# ArduinoBoardMKII.net
KiCad netlist of a schematic drawn in EAGLE
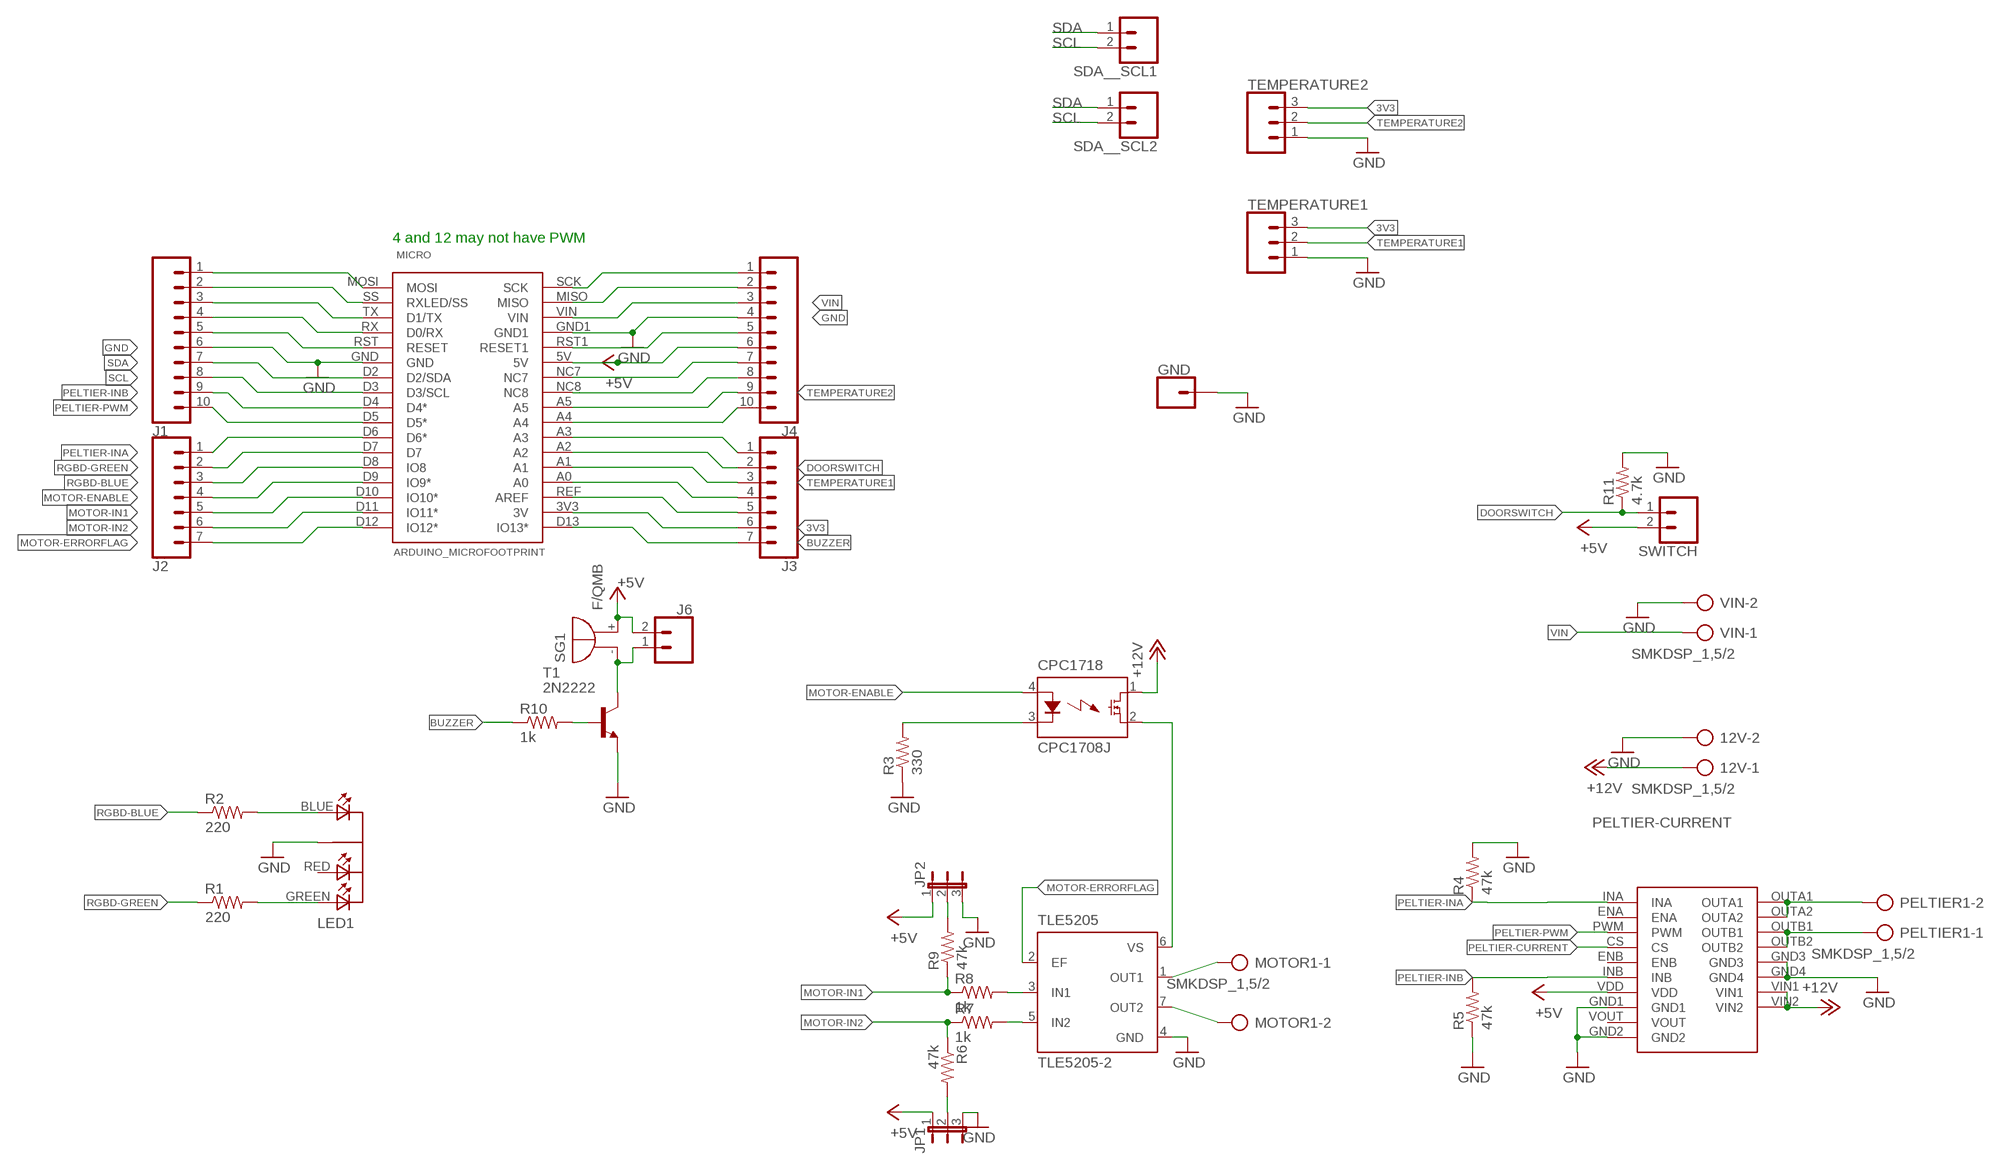
[diagram p0: schematic, sheet 1]

(export (version "E")
  (design (tool "Eeschema 10.0.6"))
  (components
    (comp (ref "12V")
      (value "SMKDSP_1,5/2")
      (footprint "eagle-import:SMKDSP_1,5_2")
      (fields (field (name "MF") "FARNELL") (field (name "MPN") "1733570"))
      (libsource (lib "eagle-import") (part "SMKDSP_1,5/2"))
    )
    (comp (ref "CPC1718")
      (value "CPC1708J")
      (footprint "eagle-import:I4-PAC")
      (libsource (lib "eagle-import") (part "CPC1708J"))
    )
    (comp (ref "GND")
      (value "CONN_01")
      (footprint "eagle-import:1X01")
      (libsource (lib "eagle-import") (part "CONN_01"))
    )
    (comp (ref "J1")
      (value "CONN_10LOCK")
      (footprint "eagle-import:1X10_LOCK")
      (libsource (lib "eagle-import") (part "CONN_10LOCK"))
    )
    (comp (ref "J2")
      (value "CONN_07LOCK")
      (footprint "eagle-import:1X07_LOCK")
      (libsource (lib "eagle-import") (part "CONN_07LOCK"))
    )
    (comp (ref "J3")
      (value "CONN_07LOCK")
      (footprint "eagle-import:1X07_LOCK")
      (libsource (lib "eagle-import") (part "CONN_07LOCK"))
    )
    (comp (ref "J4")
      (value "CONN_10LOCK")
      (footprint "eagle-import:1X10_LOCK")
      (libsource (lib "eagle-import") (part "CONN_10LOCK"))
    )
    (comp (ref "J6")
      (value "CONN_021X02_NO_SILK")
      (footprint "eagle-import:1X02_NO_SILK")
      (libsource (lib "eagle-import") (part "CONN_021X02_NO_SILK"))
    )
    (comp (ref "JP1")
      (value "JP2E")
      (footprint "eagle-import:JP2")
      (libsource (lib "eagle-import") (part "JP2E"))
    )
    (comp (ref "JP2")
      (value "JP2E")
      (footprint "eagle-import:JP2")
      (libsource (lib "eagle-import") (part "JP2E"))
    )
    (comp (ref "LED1")
      (value "LED-DIP-3")
      (footprint "eagle-import:DIP-4")
      (libsource (lib "eagle-import") (part "LED-DIP-3"))
    )
    (comp (ref "MICRO")
      (value "ARDUINO_MICROFOOTPRINT")
      (footprint "eagle-import:ARDUINO-MICRO")
      (libsource (lib "eagle-import") (part "ARDUINO_MICROFOOTPRINT"))
    )
    (comp (ref "MOTOR1")
      (value "SMKDSP_1,5/2")
      (footprint "eagle-import:SMKDSP_1,5_2")
      (fields (field (name "MF") "FARNELL") (field (name "MPN") "1733570"))
      (libsource (lib "eagle-import") (part "SMKDSP_1,5/2"))
    )
    (comp (ref "PELTIER1")
      (value "SMKDSP_1,5/2")
      (footprint "eagle-import:SMKDSP_1,5_2")
      (fields (field (name "MF") "FARNELL") (field (name "MPN") "1733570"))
      (libsource (lib "eagle-import") (part "SMKDSP_1,5/2"))
    )
    (comp (ref "R1")
      (value "220")
      (footprint "eagle-import:0207_10")
      (libsource (lib "eagle-import") (part "R-US_0207/10"))
    )
    (comp (ref "R2")
      (value "220")
      (footprint "eagle-import:0207_10")
      (libsource (lib "eagle-import") (part "R-US_0207/10"))
    )
    (comp (ref "R3")
      (value "330")
      (footprint "eagle-import:0207_10")
      (libsource (lib "eagle-import") (part "R-US_0207/10"))
    )
    (comp (ref "R4")
      (value "47k")
      (footprint "eagle-import:0207_10")
      (libsource (lib "eagle-import") (part "resistor_348_R-US_0207/10"))
    )
    (comp (ref "R5")
      (value "47k")
      (footprint "eagle-import:0207_10")
      (libsource (lib "eagle-import") (part "resistor_348_R-US_0207/10"))
    )
    (comp (ref "R6")
      (value "47k")
      (footprint "eagle-import:0207_12")
      (libsource (lib "eagle-import") (part "resistor_348_R-US_0207/12"))
    )
    (comp (ref "R7")
      (value "1k")
      (footprint "eagle-import:0207_12")
      (libsource (lib "eagle-import") (part "resistor_348_R-US_0207/12"))
    )
    (comp (ref "R8")
      (value "1k")
      (footprint "eagle-import:0207_12")
      (libsource (lib "eagle-import") (part "resistor_348_R-US_0207/12"))
    )
    (comp (ref "R9")
      (value "47k")
      (footprint "eagle-import:0207_12")
      (libsource (lib "eagle-import") (part "resistor_348_R-US_0207/12"))
    )
    (comp (ref "R10")
      (value "1k")
      (footprint "eagle-import:0207_7")
      (libsource (lib "eagle-import") (part "rcl_334_R-US_0207/7"))
    )
    (comp (ref "R11")
      (value "4.7k")
      (footprint "eagle-import:0207_10")
      (libsource (lib "eagle-import") (part "R-US_0207/10"))
    )
    (comp (ref "SDA__SCL1")
      (value "CONN_02PTH3")
      (footprint "eagle-import:1X02_LONGPADS")
      (libsource (lib "eagle-import") (part "CONN_02PTH3"))
    )
    (comp (ref "SDA__SCL2")
      (value "CONN_02PTH3")
      (footprint "eagle-import:1X02_LONGPADS")
      (libsource (lib "eagle-import") (part "CONN_02PTH3"))
    )
    (comp (ref "SG1")
      (value "F/QMB")
      (footprint "eagle-import:F_QMB")
      (libsource (lib "eagle-import") (part "F/QMB"))
    )
    (comp (ref "SWITCH")
      (value "CONN_02PTH3")
      (footprint "eagle-import:1X02_LONGPADS")
      (libsource (lib "eagle-import") (part "CONN_02PTH3"))
    )
    (comp (ref "T1")
      (value "2N2222")
      (footprint "eagle-import:TO18")
      (libsource (lib "eagle-import") (part "2N2222"))
    )
    (comp (ref "TEMPERATURE1")
      (value "CONN_03LONGPADS")
      (footprint "eagle-import:1X03_LONGPADS")
      (libsource (lib "eagle-import") (part "CONN_03LONGPADS"))
    )
    (comp (ref "TEMPERATURE2")
      (value "CONN_03LONGPADS")
      (footprint "eagle-import:1X03_LONGPADS")
      (libsource (lib "eagle-import") (part "CONN_03LONGPADS"))
    )
    (comp (ref "TLE5205")
      (value "TLE5205-2")
      (footprint "eagle-import:P-TO220-7-11")
      (libsource (lib "eagle-import") (part "TLE5205-2"))
    )
    (comp (ref "VIN")
      (value "SMKDSP_1,5/2")
      (footprint "eagle-import:SMKDSP_1,5_2")
      (fields (field (name "MF") "FARNELL") (field (name "MPN") "1733570"))
      (libsource (lib "eagle-import") (part "SMKDSP_1,5/2"))
    )
    (comp (ref "VNH5019")
      (value "VNH5019VNH5019BOARD")
      (footprint "eagle-import:DIP3302W60P254L2400H500Q20B")
      (libsource (lib "eagle-import") (part "VNH5019VNH5019BOARD"))
    )
  )
  (nets
    (net (code "1") (name "+5V") (class "Default")
      (node (ref "J4") (pin "6") (pinfunction "6_6") (pintype "passive"))
      (node (ref "J6") (pin "2") (pinfunction "2_2") (pintype "passive"))
      (node (ref "JP1") (pin "1") (pinfunction "1_1") (pintype "passive"))
      (node (ref "JP2") (pin "1") (pinfunction "1_1") (pintype "passive"))
      (node (ref "MICRO") (pin "5V") (pinfunction "5V_5V") (pintype "bidirectional"))
      (node (ref "SG1") (pin "+") (pinfunction "-_+") (pintype "passive"))
      (node (ref "SWITCH") (pin "2") (pinfunction "2_2") (pintype "passive"))
      (node (ref "VNH5019") (pin "VDD") (pinfunction "VDD_VDD") (pintype "bidirectional"))
    )
    (net (code "2") (name "+12V") (class "Default")
      (node (ref "12V") (pin "1") (pinfunction "KL_1") (pintype "passive"))
      (node (ref "CPC1718") (pin "1") (pinfunction "DS1_1") (pintype "passive"))
      (node (ref "VNH5019") (pin "VIN1") (pinfunction "VIN1_VIN1") (pintype "bidirectional"))
      (node (ref "VNH5019") (pin "VIN2") (pinfunction "VIN2_VIN2") (pintype "bidirectional"))
    )
    (net (code "3") (name "3V3") (class "Default")
      (node (ref "J3") (pin "6") (pinfunction "6_6") (pintype "passive"))
      (node (ref "MICRO") (pin "3V3") (pinfunction "3V_3V3") (pintype "bidirectional"))
      (node (ref "TEMPERATURE1") (pin "3") (pinfunction "3_3") (pintype "passive"))
      (node (ref "TEMPERATURE2") (pin "3") (pinfunction "3_3") (pintype "passive"))
    )
    (net (code "4") (name "BUZZER") (class "Default")
      (node (ref "J3") (pin "7") (pinfunction "7_7") (pintype "passive"))
      (node (ref "MICRO") (pin "D13") (pinfunction "IO13*_D13") (pintype "bidirectional"))
      (node (ref "R10") (pin "1") (pinfunction "1_1") (pintype "passive"))
    )
    (net (code "5") (name "DOORSWITCH") (class "Default")
      (node (ref "J3") (pin "2") (pinfunction "2_2") (pintype "passive"))
      (node (ref "MICRO") (pin "A2") (pinfunction "A2_A2") (pintype "bidirectional"))
      (node (ref "R11") (pin "1") (pinfunction "1_1") (pintype "passive"))
      (node (ref "SWITCH") (pin "1") (pinfunction "1_1") (pintype "passive"))
    )
    (net (code "6") (name "GND") (class "Default")
      (node (ref "12V") (pin "2") (pinfunction "KL_2") (pintype "passive"))
      (node (ref "GND") (pin "1") (pinfunction "1_1") (pintype "passive"))
      (node (ref "J1") (pin "6") (pinfunction "6_6") (pintype "passive"))
      (node (ref "J4") (pin "4") (pinfunction "4_4") (pintype "passive"))
      (node (ref "JP1") (pin "3") (pinfunction "3_3") (pintype "passive"))
      (node (ref "JP2") (pin "3") (pinfunction "3_3") (pintype "passive"))
      (node (ref "LED1") (pin "COMMON_CATHODE") (pinfunction "COM-CATHODE_COMMON_CATHODE") (pintype "passive"))
      (node (ref "MICRO") (pin "GND") (pinfunction "GND_GND") (pintype "bidirectional"))
      (node (ref "MICRO") (pin "GND1") (pinfunction "GND1_GND1") (pintype "bidirectional"))
      (node (ref "R11") (pin "2") (pinfunction "2_2") (pintype "passive"))
      (node (ref "R3") (pin "1") (pinfunction "1_1") (pintype "passive"))
      (node (ref "R4") (pin "2") (pinfunction "2_2") (pintype "passive"))
      (node (ref "R5") (pin "1") (pinfunction "1_1") (pintype "passive"))
      (node (ref "T1") (pin "1") (pinfunction "E_1") (pintype "passive"))
      (node (ref "TEMPERATURE1") (pin "1") (pinfunction "1_1") (pintype "passive"))
      (node (ref "TEMPERATURE2") (pin "1") (pinfunction "1_1") (pintype "passive"))
      (node (ref "TLE5205") (pin "4") (pinfunction "GND_4") (pintype "power_in"))
      (node (ref "VIN") (pin "2") (pinfunction "KL_2") (pintype "passive"))
      (node (ref "VNH5019") (pin "GND1") (pinfunction "GND1_GND1") (pintype "bidirectional"))
      (node (ref "VNH5019") (pin "GND2") (pinfunction "GND2_GND2") (pintype "bidirectional"))
      (node (ref "VNH5019") (pin "GND3") (pinfunction "GND3_GND3") (pintype "bidirectional"))
      (node (ref "VNH5019") (pin "GND4") (pinfunction "GND4_GND4") (pintype "bidirectional"))
    )
    (net (code "7") (name "MOTOR-ENABLE") (class "Default")
      (node (ref "CPC1718") (pin "4") (pinfunction "A_4") (pintype "passive"))
      (node (ref "J2") (pin "4") (pinfunction "4_4") (pintype "passive"))
      (node (ref "MICRO") (pin "D9") (pinfunction "IO9*_D9") (pintype "bidirectional"))
    )
    (net (code "8") (name "MOTOR-ERRORFLAG") (class "Default")
      (node (ref "J2") (pin "7") (pinfunction "7_7") (pintype "passive"))
      (node (ref "MICRO") (pin "D12") (pinfunction "IO12*_D12") (pintype "bidirectional"))
      (node (ref "TLE5205") (pin "2") (pinfunction "EF_2") (pintype "open_collector"))
    )
    (net (code "9") (name "MOTOR-IN1") (class "Default")
      (node (ref "J2") (pin "5") (pinfunction "5_5") (pintype "passive"))
      (node (ref "MICRO") (pin "D10") (pinfunction "IO10*_D10") (pintype "bidirectional"))
      (node (ref "R8") (pin "1") (pinfunction "1_1") (pintype "passive"))
      (node (ref "R9") (pin "1") (pinfunction "1_1") (pintype "passive"))
    )
    (net (code "10") (name "MOTOR-IN2") (class "Default")
      (node (ref "J2") (pin "6") (pinfunction "6_6") (pintype "passive"))
      (node (ref "MICRO") (pin "D11") (pinfunction "IO11*_D11") (pintype "bidirectional"))
      (node (ref "R6") (pin "1") (pinfunction "1_1") (pintype "passive"))
      (node (ref "R7") (pin "1") (pinfunction "1_1") (pintype "passive"))
    )
    (net (code "11") (name "Net-(CPC1718-DS2)") (class "Default")
      (node (ref "CPC1718") (pin "2") (pinfunction "DS2_2") (pintype "passive"))
      (node (ref "TLE5205") (pin "6") (pinfunction "VS_6") (pintype "input"))
    )
    (net (code "12") (name "Net-(CPC1718-K)") (class "Default")
      (node (ref "CPC1718") (pin "3") (pinfunction "K_3") (pintype "passive"))
      (node (ref "R3") (pin "2") (pinfunction "2_2") (pintype "passive"))
    )
    (net (code "13") (name "Net-(J1-Pad1)") (class "Default")
      (node (ref "J1") (pin "1") (pinfunction "1_1") (pintype "passive"))
      (node (ref "MICRO") (pin "MOSI") (pinfunction "MOSI_MOSI") (pintype "bidirectional"))
    )
    (net (code "14") (name "Net-(J3-Pad1)") (class "Default")
      (node (ref "J3") (pin "1") (pinfunction "1_1") (pintype "passive"))
      (node (ref "MICRO") (pin "A3") (pinfunction "A3_A3") (pintype "bidirectional"))
    )
    (net (code "15") (name "Net-(J3-Pad4)") (class "Default")
      (node (ref "J3") (pin "4") (pinfunction "4_4") (pintype "passive"))
      (node (ref "MICRO") (pin "A0") (pinfunction "A0_A0") (pintype "bidirectional"))
    )
    (net (code "16") (name "Net-(J4-Pad1)") (class "Default")
      (node (ref "J4") (pin "1") (pinfunction "1_1") (pintype "passive"))
      (node (ref "MICRO") (pin "SCK") (pinfunction "SCK_SCK") (pintype "bidirectional"))
    )
    (net (code "17") (name "Net-(J4-Pad2)") (class "Default")
      (node (ref "J4") (pin "2") (pinfunction "2_2") (pintype "passive"))
      (node (ref "MICRO") (pin "MISO") (pinfunction "MISO_MISO") (pintype "bidirectional"))
    )
    (net (code "18") (name "Net-(J4-Pad7)") (class "Default")
      (node (ref "J4") (pin "7") (pinfunction "7_7") (pintype "passive"))
      (node (ref "MICRO") (pin "NC7") (pinfunction "NC7_NC7") (pintype "bidirectional"))
    )
    (net (code "19") (name "Net-(J4-Pad8)") (class "Default")
      (node (ref "J4") (pin "8") (pinfunction "8_8") (pintype "passive"))
      (node (ref "MICRO") (pin "NC8") (pinfunction "NC8_NC8") (pintype "bidirectional"))
    )
    (net (code "20") (name "Net-(J4-Pad10)") (class "Default")
      (node (ref "J4") (pin "10") (pinfunction "10_10") (pintype "passive"))
      (node (ref "MICRO") (pin "A4") (pinfunction "A4_A4") (pintype "bidirectional"))
    )
    (net (code "21") (name "Net-(JP1-Pad2)") (class "Default")
      (node (ref "JP1") (pin "2") (pinfunction "2_2") (pintype "passive"))
      (node (ref "R6") (pin "2") (pinfunction "2_2") (pintype "passive"))
    )
    (net (code "22") (name "Net-(JP2-Pad2)") (class "Default")
      (node (ref "JP2") (pin "2") (pinfunction "2_2") (pintype "passive"))
      (node (ref "R9") (pin "2") (pinfunction "2_2") (pintype "passive"))
    )
    (net (code "23") (name "Net-(LED1-PadBLUE)") (class "Default")
      (node (ref "LED1") (pin "BLUE") (pinfunction "BLUE_BLUE") (pintype "passive"))
      (node (ref "R2") (pin "2") (pinfunction "2_2") (pintype "passive"))
    )
    (net (code "24") (name "Net-(LED1-PadGREEN)") (class "Default")
      (node (ref "LED1") (pin "GREEN") (pinfunction "GREEN_GREEN") (pintype "passive"))
      (node (ref "R1") (pin "2") (pinfunction "2_2") (pintype "passive"))
    )
    (net (code "25") (name "Net-(MICRO-AREF)") (class "Default")
      (node (ref "J3") (pin "5") (pinfunction "5_5") (pintype "passive"))
      (node (ref "MICRO") (pin "REF") (pinfunction "AREF_REF") (pintype "bidirectional"))
    )
    (net (code "26") (name "Net-(MICRO-D0{slash}RX)") (class "Default")
      (node (ref "J1") (pin "4") (pinfunction "4_4") (pintype "passive"))
      (node (ref "MICRO") (pin "RX") (pinfunction "D0/RX_RX") (pintype "bidirectional"))
    )
    (net (code "27") (name "Net-(MICRO-D1{slash}TX)") (class "Default")
      (node (ref "J1") (pin "3") (pinfunction "3_3") (pintype "passive"))
      (node (ref "MICRO") (pin "TX") (pinfunction "D1/TX_TX") (pintype "bidirectional"))
    )
    (net (code "28") (name "Net-(MICRO-RESET)") (class "Default")
      (node (ref "J1") (pin "5") (pinfunction "5_5") (pintype "passive"))
      (node (ref "MICRO") (pin "RST") (pinfunction "RESET_RST") (pintype "bidirectional"))
    )
    (net (code "29") (name "Net-(MICRO-RESET1)") (class "Default")
      (node (ref "J4") (pin "5") (pinfunction "5_5") (pintype "passive"))
      (node (ref "MICRO") (pin "RST1") (pinfunction "RESET1_RST1") (pintype "bidirectional"))
    )
    (net (code "30") (name "Net-(MICRO-RXLED{slash}SS)") (class "Default")
      (node (ref "J1") (pin "2") (pinfunction "2_2") (pintype "passive"))
      (node (ref "MICRO") (pin "SS") (pinfunction "RXLED/SS_SS") (pintype "bidirectional"))
    )
    (net (code "31") (name "Net-(MOTOR1A-KL)") (class "Default")
      (node (ref "MOTOR1") (pin "1") (pinfunction "KL_1") (pintype "passive"))
      (node (ref "TLE5205") (pin "1") (pinfunction "OUT1_1") (pintype "output"))
    )
    (net (code "32") (name "Net-(MOTOR1B-KL)") (class "Default")
      (node (ref "MOTOR1") (pin "2") (pinfunction "KL_2") (pintype "passive"))
      (node (ref "TLE5205") (pin "7") (pinfunction "OUT2_7") (pintype "output"))
    )
    (net (code "33") (name "Net-(PELTIER1A-KL)") (class "Default")
      (node (ref "PELTIER1") (pin "1") (pinfunction "KL_1") (pintype "passive"))
      (node (ref "VNH5019") (pin "OUTB1") (pinfunction "OUTB1_OUTB1") (pintype "bidirectional"))
      (node (ref "VNH5019") (pin "OUTB2") (pinfunction "OUTB2_OUTB2") (pintype "bidirectional"))
    )
    (net (code "34") (name "Net-(PELTIER1B-KL)") (class "Default")
      (node (ref "PELTIER1") (pin "2") (pinfunction "KL_2") (pintype "passive"))
      (node (ref "VNH5019") (pin "OUTA1") (pinfunction "OUTA1_OUTA1") (pintype "bidirectional"))
      (node (ref "VNH5019") (pin "OUTA2") (pinfunction "OUTA2_OUTA2") (pintype "bidirectional"))
    )
    (net (code "35") (name "Net-(SG1-+)") (class "Default")
      (node (ref "J6") (pin "1") (pinfunction "1_1") (pintype "passive"))
      (node (ref "SG1") (pin "-") (pinfunction "+_-") (pintype "passive"))
      (node (ref "T1") (pin "3") (pinfunction "C_3") (pintype "passive"))
    )
    (net (code "36") (name "Net-(T1-B)") (class "Default")
      (node (ref "R10") (pin "2") (pinfunction "2_2") (pintype "passive"))
      (node (ref "T1") (pin "2") (pinfunction "B_2") (pintype "passive"))
    )
    (net (code "37") (name "Net-(TLE5205-IN1)") (class "Default")
      (node (ref "R8") (pin "2") (pinfunction "2_2") (pintype "passive"))
      (node (ref "TLE5205") (pin "3") (pinfunction "IN1_3") (pintype "input"))
    )
    (net (code "38") (name "Net-(TLE5205-IN2)") (class "Default")
      (node (ref "R7") (pin "2") (pinfunction "2_2") (pintype "passive"))
      (node (ref "TLE5205") (pin "5") (pinfunction "IN2_5") (pintype "input"))
    )
    (net (code "39") (name "PELTIER-CURRENT") (class "Default")
      (node (ref "VNH5019") (pin "CS") (pinfunction "CS_CS") (pintype "bidirectional"))
    )
    (net (code "40") (name "PELTIER-INA") (class "Default")
      (node (ref "J2") (pin "1") (pinfunction "1_1") (pintype "passive"))
      (node (ref "MICRO") (pin "D6") (pinfunction "D6*_D6") (pintype "bidirectional"))
      (node (ref "R4") (pin "1") (pinfunction "1_1") (pintype "passive"))
      (node (ref "VNH5019") (pin "INA") (pinfunction "INA_INA") (pintype "bidirectional"))
    )
    (net (code "41") (name "PELTIER-INB") (class "Default")
      (node (ref "J1") (pin "9") (pinfunction "9_9") (pintype "passive"))
      (node (ref "MICRO") (pin "D4") (pinfunction "D4*_D4") (pintype "bidirectional"))
      (node (ref "R5") (pin "2") (pinfunction "2_2") (pintype "passive"))
      (node (ref "VNH5019") (pin "INB") (pinfunction "INB_INB") (pintype "bidirectional"))
    )
    (net (code "42") (name "PELTIER-PWM") (class "Default")
      (node (ref "J1") (pin "10") (pinfunction "10_10") (pintype "passive"))
      (node (ref "MICRO") (pin "D5") (pinfunction "D5*_D5") (pintype "bidirectional"))
      (node (ref "VNH5019") (pin "PWM") (pinfunction "PWM_PWM") (pintype "bidirectional"))
    )
    (net (code "43") (name "RGBD-BLUE") (class "Default")
      (node (ref "J2") (pin "3") (pinfunction "3_3") (pintype "passive"))
      (node (ref "MICRO") (pin "D8") (pinfunction "IO8_D8") (pintype "bidirectional"))
      (node (ref "R2") (pin "1") (pinfunction "1_1") (pintype "passive"))
    )
    (net (code "44") (name "RGBD-GREEN") (class "Default")
      (node (ref "J2") (pin "2") (pinfunction "2_2") (pintype "passive"))
      (node (ref "MICRO") (pin "D7") (pinfunction "D7_D7") (pintype "bidirectional"))
      (node (ref "R1") (pin "1") (pinfunction "1_1") (pintype "passive"))
    )
    (net (code "45") (name "SCL") (class "Default")
      (node (ref "J1") (pin "8") (pinfunction "8_8") (pintype "passive"))
      (node (ref "MICRO") (pin "D3") (pinfunction "D3/SCL_D3") (pintype "bidirectional"))
      (node (ref "SDA__SCL1") (pin "2") (pinfunction "2_2") (pintype "passive"))
      (node (ref "SDA__SCL2") (pin "2") (pinfunction "2_2") (pintype "passive"))
    )
    (net (code "46") (name "SDA") (class "Default")
      (node (ref "J1") (pin "7") (pinfunction "7_7") (pintype "passive"))
      (node (ref "MICRO") (pin "D2") (pinfunction "D2/SDA_D2") (pintype "bidirectional"))
      (node (ref "SDA__SCL1") (pin "1") (pinfunction "1_1") (pintype "passive"))
      (node (ref "SDA__SCL2") (pin "1") (pinfunction "1_1") (pintype "passive"))
    )
    (net (code "47") (name "TEMPERATURE1") (class "Default")
      (node (ref "J3") (pin "3") (pinfunction "3_3") (pintype "passive"))
      (node (ref "MICRO") (pin "A1") (pinfunction "A1_A1") (pintype "bidirectional"))
      (node (ref "TEMPERATURE1") (pin "2") (pinfunction "2_2") (pintype "passive"))
    )
    (net (code "48") (name "TEMPERATURE2") (class "Default")
      (node (ref "J4") (pin "9") (pinfunction "9_9") (pintype "passive"))
      (node (ref "MICRO") (pin "A5") (pinfunction "A5_A5") (pintype "bidirectional"))
      (node (ref "TEMPERATURE2") (pin "2") (pinfunction "2_2") (pintype "passive"))
    )
    (net (code "49") (name "VIN") (class "Default")
      (node (ref "J4") (pin "3") (pinfunction "3_3") (pintype "passive"))
      (node (ref "MICRO") (pin "VIN") (pinfunction "VIN_VIN") (pintype "bidirectional"))
      (node (ref "VIN") (pin "1") (pinfunction "KL_1") (pintype "passive"))
    )
    (net (code "50") (name "unconnected-(LED1-PadRED)") (class "Default")
      (node (ref "LED1") (pin "RED") (pinfunction "RED_RED") (pintype "passive"))
    )
    (net (code "51") (name "unconnected-(VNH5019-PadENA)") (class "Default")
      (node (ref "VNH5019") (pin "ENA") (pinfunction "ENA_ENA") (pintype "bidirectional"))
    )
    (net (code "52") (name "unconnected-(VNH5019-PadENB)") (class "Default")
      (node (ref "VNH5019") (pin "ENB") (pinfunction "ENB_ENB") (pintype "bidirectional"))
    )
    (net (code "53") (name "unconnected-(VNH5019-PadVOUT)") (class "Default")
      (node (ref "VNH5019") (pin "VOUT") (pinfunction "VOUT_VOUT") (pintype "bidirectional"))
    )
  )
)
